# SH6_-_17V_POWER.net
KiCad netlist of a schematic drawn in Altium Designer
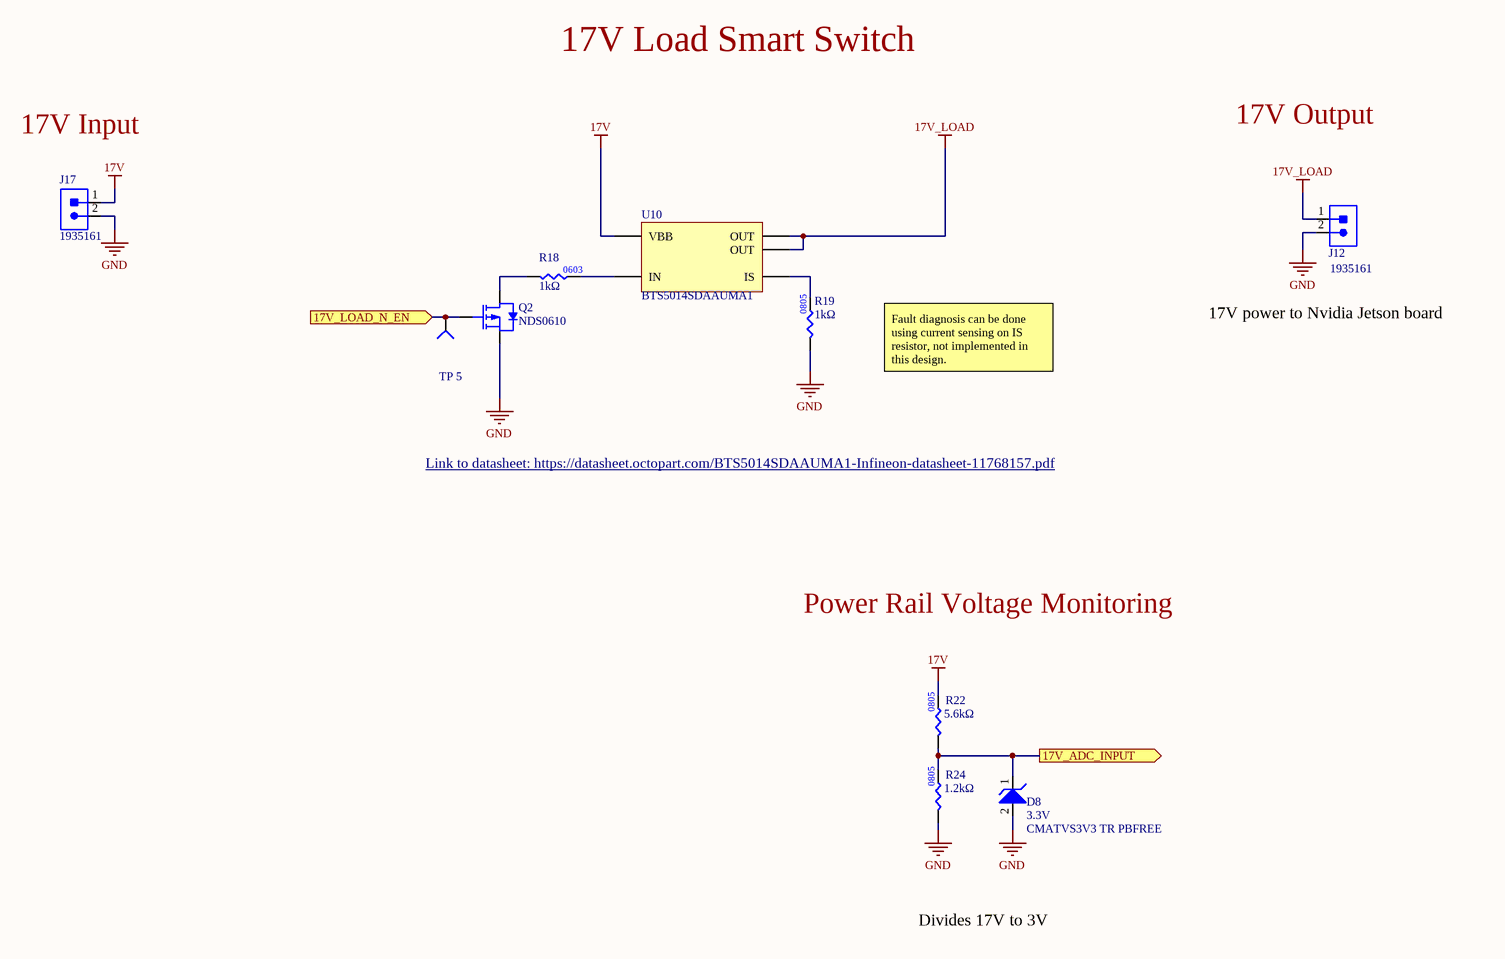
[diagram p0: SH6 - 17V POWER.SchDoc]

(export (version "E")
  (design (tool "Eeschema 10.0.6"))
  (components
    (comp (ref "D8")
      (value "TVS_DIODE_UNIDIR_3.3V_7A")
      (footprint "SOD-923")
      (description "TVS DIODE 3.3VWM 11VC SOD923")
      (fields
        (field (name "MANUFACTURER PART NUMBER 1") "CMATVS3V3 TR PBFREE")
        (field (name "VOLTAGE - REVERSE STANDOFF (TYP)") "3.3V")
      )
      (libsource (lib "UWRT_Schematic_Library_2020") (part "TVS_DIODE_UNIDIR_3.3V_7A"))
    )
    (comp (ref "J12")
      (value "CON_2M_TERM")
      (footprint "1935161")
      (description "TERM BLK 2POS SIDE ENTRY 5MM")
      (fields (field (name "VOLTAGE") "300V") (field (name "MANUFACTURER PART NUMBER 1") "1935161"))
      (libsource (lib "UWRT_Schematic_Library_2020") (part "CON_2M_TERM"))
    )
    (comp (ref "J17")
      (value "CON_2M_TERM")
      (footprint "1935161")
      (description "TERM BLK 2POS SIDE ENTRY 5MM")
      (fields (field (name "VOLTAGE") "300V") (field (name "MANUFACTURER PART NUMBER 1") "1935161"))
      (libsource (lib "") (part "CON_2M_TERM_1"))
    )
    (comp (ref "Q2")
      (value "PMOS_60V_120mA")
      (footprint "SOT23-3")
      (description "MOSFET P-CH 60V 120MA SOT-23")
      (fields (field (name "MANUFACTURER PART NUMBER 1") "NDS0610"))
      (libsource (lib "UWRT_Schematic_Library_2020") (part "PMOS_60V_120mA"))
    )
    (comp (ref "R18")
      (value "1kΩ")
      (footprint "RES0603")
      (description "RES 1K OHM 5% 1/10W 0603")
      (fields (field (name "Comment") "RES_1kΩ_0603_5%"))
      (libsource (lib "UWRT_Schematic_Library_2020") (part "RES_1kΩ_0603_5%"))
    )
    (comp (ref "R19")
      (value "1kΩ")
      (footprint "RES0805")
      (description "RES 1K OHM 1% 1/8W 0805")
      (fields (field (name "LCSC PART #") "C17513") (field (name "Comment") "RES_1kΩ_0805_1%"))
      (libsource (lib "UWRT_Schematic_Library_2020") (part "RES_1kΩ_0805_1%"))
    )
    (comp (ref "R22")
      (value "5.6kΩ")
      (footprint "RES0805")
      (description "RES 5.6K OHM 5% 1/8W 0805")
      (fields (field (name "TOLERANCE") "5%") (field (name "Comment") "RES_5.6kΩ_0805"))
      (libsource (lib "UWRT_Schematic_Library_2020") (part "RES_5.6kΩ_0805_5%"))
    )
    (comp (ref "R24")
      (value "1.2kΩ")
      (footprint "RES0805")
      (description "RES 1.2K OHM 5% 1/8W 0805")
      (fields (field (name "TOLERANCE") "5%") (field (name "Comment") "RES_1.2kΩ_0805"))
      (libsource (lib "UWRT_Schematic_Library_2020") (part "RES_1.2kΩ_0805_5%"))
    )
    (comp (ref "TP 5")
      (value "TESTPOINT_1MM_CIRCLE")
      (footprint "TESTPOINT_CIRCLE_1MM")
      (description "TESTPOINT 1MM CIRCLE")
      (libsource (lib "UWRT_Schematic_Library_2020") (part "TESTPOINT_1MM_CIRCLE"))
    )
    (comp (ref "U10")
      (value "BTS5014SDAAUMA1")
      (footprint "D2PAK-4")
      (description "IC PWR SWITCH N-CHAN 1:1 TO252-5")
      (fields (field (name "MANUFACTURER PART NUMBER 1") "BTS5014SDAAUMA1"))
      (libsource (lib "UWRT_Schematic_Library_2020") (part "BTS5014SDAAUMA1"))
    )
  )
  (nets
    (net (code "1") (name "/17V_ADC_INPUT") (class "Default")
      (node (ref "D8") (pin "1") (pinfunction "1_1") (pintype "passive"))
      (node (ref "R22") (pin "1") (pinfunction "1_1") (pintype "passive"))
      (node (ref "R24") (pin "2") (pinfunction "2_2") (pintype "passive"))
    )
    (net (code "2") (name "/17V_LOAD_N_EN") (class "Default")
      (node (ref "Q2") (pin "1") (pinfunction "Gate_1") (pintype "passive"))
      (node (ref "TP 5") (pin "1") (pinfunction "=value_1") (pintype "passive"))
    )
    (net (code "3") (name "17V") (class "Default")
      (node (ref "J17") (pin "1") (pinfunction "1_1") (pintype "passive"))
      (node (ref "R22") (pin "2") (pinfunction "2_2") (pintype "passive"))
      (node (ref "U10") (pin "3") (pinfunction "VBB_3") (pintype "passive"))
    )
    (net (code "4") (name "17V_LOAD") (class "Default")
      (node (ref "J12") (pin "1") (pinfunction "1_1") (pintype "passive"))
      (node (ref "U10") (pin "1") (pinfunction "OUT_1") (pintype "passive"))
      (node (ref "U10") (pin "5") (pinfunction "OUT_5") (pintype "passive"))
    )
    (net (code "5") (name "GND") (class "Default")
      (node (ref "D8") (pin "2") (pinfunction "2_2") (pintype "passive"))
      (node (ref "J12") (pin "2") (pinfunction "2_2") (pintype "passive"))
      (node (ref "J17") (pin "2") (pinfunction "2_2") (pintype "passive"))
      (node (ref "Q2") (pin "2") (pinfunction "Source_2") (pintype "passive"))
      (node (ref "R19") (pin "1") (pinfunction "1_1") (pintype "passive"))
      (node (ref "R24") (pin "1") (pinfunction "1_1") (pintype "passive"))
    )
    (net (code "6") (name "Net-(Q2-Drain)") (class "Default")
      (node (ref "Q2") (pin "3") (pinfunction "Drain_3") (pintype "passive"))
      (node (ref "R18") (pin "1") (pinfunction "1_1") (pintype "passive"))
    )
    (net (code "7") (name "Net-(U10-IN)") (class "Default")
      (node (ref "R18") (pin "2") (pinfunction "2_2") (pintype "passive"))
      (node (ref "U10") (pin "2") (pinfunction "IN_2") (pintype "passive"))
    )
    (net (code "8") (name "Net-(U10-IS)") (class "Default")
      (node (ref "R19") (pin "2") (pinfunction "2_2") (pintype "passive"))
      (node (ref "U10") (pin "4") (pinfunction "IS_4") (pintype "passive"))
    )
  )
)
